# soic-8_breakout.net
KiCad netlist of a schematic drawn in EAGLE
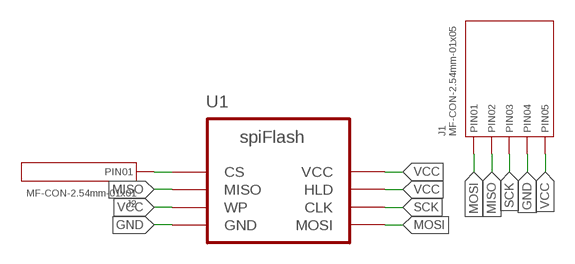
[diagram p0: schematic, sheet 1]

(export (version "E")
  (design (tool "Eeschema 10.0.6"))
  (components
    (comp (ref "J1")
      (value "MF-CON-2.54mm-01x05")
      (footprint "eagle-import:PTH_2.54MM_01X05")
      (fields (field (name "HOUSEPART") "YES"))
      (libsource (lib "eagle-import") (part "CON_01X05_PTH_2.54MM"))
    )
    (comp (ref "J2")
      (value "MF-CON-2.54mm-01x01")
      (footprint "eagle-import:PTH_2.54MM_01X01")
      (fields (field (name "HOUSEPART") "YES"))
      (libsource (lib "eagle-import") (part "CON_01X01_PTH_2.54MM"))
    )
    (comp (ref "U1")
      (value "WINBOND_FLASH_4MBIT-SOIC")
      (footprint "eagle-import:SOIC8")
      (libsource (lib "eagle-import") (part "WINBOND_FLASH_4MBIT-SOIC"))
    )
  )
  (nets
    (net (code "1") (name "GND") (class "Default")
      (node (ref "J1") (pin "P$4") (pinfunction "PIN4_P$4") (pintype "bidirectional"))
      (node (ref "U1") (pin "4") (pinfunction "GND_4") (pintype "bidirectional"))
    )
    (net (code "2") (name "MISO") (class "Default")
      (node (ref "J1") (pin "P$2") (pinfunction "PIN2_P$2") (pintype "bidirectional"))
      (node (ref "U1") (pin "2") (pinfunction "MISO_2") (pintype "bidirectional"))
    )
    (net (code "3") (name "MOSI") (class "Default")
      (node (ref "J1") (pin "P$1") (pinfunction "PIN1_P$1") (pintype "bidirectional"))
      (node (ref "U1") (pin "5") (pinfunction "MOSI_5") (pintype "bidirectional"))
    )
    (net (code "4") (name "Net-(J2-PIN1)") (class "Default")
      (node (ref "J2") (pin "P$1") (pinfunction "PIN1_P$1") (pintype "bidirectional"))
      (node (ref "U1") (pin "1") (pinfunction "CS_1") (pintype "bidirectional"))
    )
    (net (code "5") (name "SCK") (class "Default")
      (node (ref "J1") (pin "P$3") (pinfunction "PIN3_P$3") (pintype "bidirectional"))
      (node (ref "U1") (pin "6") (pinfunction "CLK_6") (pintype "bidirectional"))
    )
    (net (code "6") (name "VCC") (class "Default")
      (node (ref "J1") (pin "P$5") (pinfunction "PIN5_P$5") (pintype "bidirectional"))
      (node (ref "U1") (pin "3") (pinfunction "WP_3") (pintype "bidirectional"))
      (node (ref "U1") (pin "7") (pinfunction "HLD_7") (pintype "bidirectional"))
      (node (ref "U1") (pin "8") (pinfunction "VCC_8") (pintype "bidirectional"))
    )
  )
)
